# Fonte.net
KiCad netlist of a schematic drawn in Altium Designer
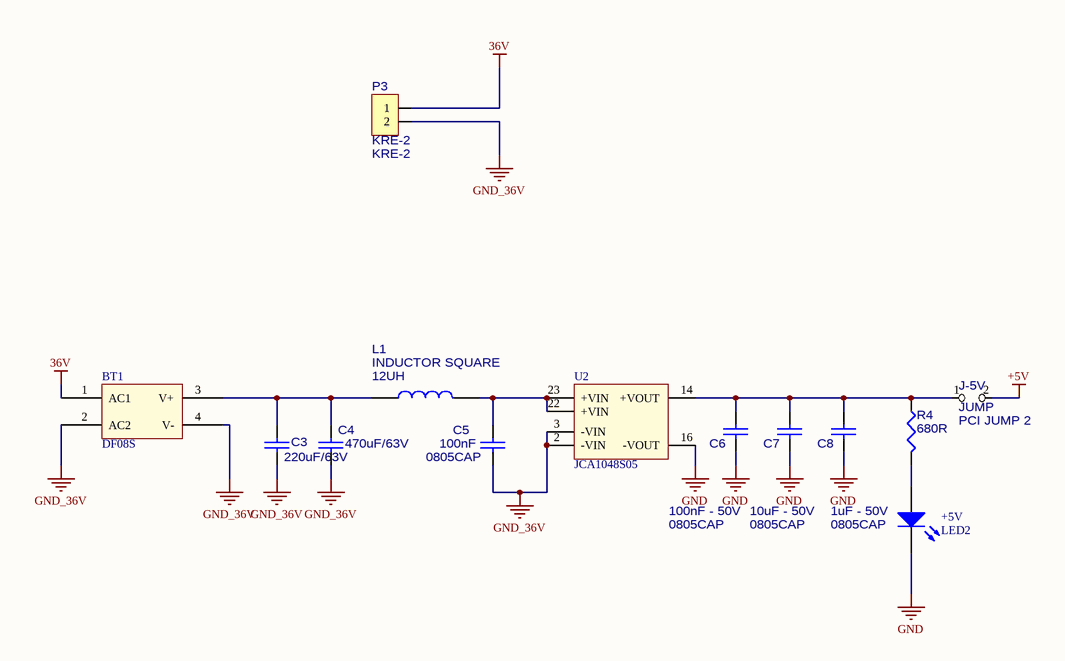
[diagram p0: Fonte.SchDoc]

(export (version "E")
  (design (tool "Eeschema 10.0.6"))
  (components
    (comp (ref "+5V")
      (value "LED2")
      (footprint "3.2X1.6X1.1")
      (description "Typical RED, GREEN, YELLOW, AMBER GaAs LED")
      (fields (field (name "PUBLISHER") "Altium Limited"))
      (libsource (lib "Miscellaneous Devices") (part "LED2"))
    )
    (comp (ref "BT1")
      (value "DF08S")
      (footprint "DF-S")
      (libsource (lib "Desafio_Hardware_Firmware_Nathania") (part "DF08S"))
    )
    (comp (ref "C3")
      (value "220uF/63V")
      (footprint "CAP_ELET_SMD_10x13.5")
      (libsource (lib "PMU_LIBRARY") (part "CAP"))
    )
    (comp (ref "C4")
      (value "470uF/63V")
      (footprint "CAP_ELET_SMD_10x13.5")
      (libsource (lib "PMU_LIBRARY") (part "CAP"))
    )
    (comp (ref "C5") (value "100nF") (footprint "0805CAP") (libsource (lib "PMU_LIBRARY") (part "CAP")))
    (comp (ref "C6") (value "100nF - 50V") (footprint "0805CAP") (libsource (lib "PMU_LIBRARY") (part "CAP")))
    (comp (ref "C7") (value "10uF - 50V") (footprint "0805CAP") (libsource (lib "PMU_LIBRARY") (part "CAP")))
    (comp (ref "C8") (value "1uF - 50V") (footprint "0805CAP") (libsource (lib "PMU_LIBRARY") (part "CAP")))
    (comp (ref "J-5V") (value "JUMP") (footprint "PCI JUMP 2") (libsource (lib "EMANUEL") (part "JUMP")))
    (comp (ref "L1")
      (value "12UH")
      (footprint "INDUCTOR SQUARE")
      (description "Inductor")
      (fields (field (name "Comment") "470UH"))
      (libsource (lib "*") (part "IND"))
    )
    (comp (ref "P3")
      (value "KRE-2")
      (footprint "KRE-2")
      (libsource (lib "Desafio_Hardware_Firmware_Nathania") (part "CON2_2_2"))
    )
    (comp (ref "R4")
      (value "680R")
      (footprint "0805RES")
      (description "2.2 Ohm 5% 1/16W 0603 RES SMT")
      (libsource (lib "EMANUEL") (part "Res0805"))
    )
    (comp (ref "U2")
      (value "JCA1048S05")
      (footprint "SCW05")
      (libsource (lib "TELEMETRIA_U_M_V1.0") (part "SCW05"))
    )
  )
  (nets
    (net (code "1") (name "+5V") (class "Default") (node (ref "J-5V") (pin "2") (pintype "passive")))
    (net (code "2") (name "36V") (class "Default")
      (node (ref "BT1") (pin "1") (pinfunction "AC1_1") (pintype "passive"))
      (node (ref "P3") (pin "1") (pinfunction "1_1") (pintype "passive"))
    )
    (net (code "3") (name "GND") (class "Default")
      (node (ref "+5V") (pin "2") (pinfunction "K_2") (pintype "passive"))
      (node (ref "C6") (pin "2") (pintype "passive"))
      (node (ref "C7") (pin "2") (pintype "passive"))
      (node (ref "C8") (pin "2") (pintype "passive"))
      (node (ref "U2") (pin "16") (pinfunction "-VOUT_16") (pintype "passive"))
    )
    (net (code "4") (name "GND_36V") (class "Default")
      (node (ref "BT1") (pin "2") (pinfunction "AC2_2") (pintype "passive"))
      (node (ref "BT1") (pin "4") (pinfunction "V-_4") (pintype "passive"))
      (node (ref "C3") (pin "1") (pintype "passive"))
      (node (ref "C4") (pin "1") (pintype "passive"))
      (node (ref "C5") (pin "2") (pintype "passive"))
      (node (ref "P3") (pin "2") (pinfunction "2_2") (pintype "passive"))
      (node (ref "U2") (pin "2") (pinfunction "-VIN_2") (pintype "passive"))
      (node (ref "U2") (pin "3") (pinfunction "-VIN_3") (pintype "passive"))
    )
    (net (code "5") (name "Net-(+5V-A)") (class "Default")
      (node (ref "+5V") (pin "1") (pinfunction "A_1") (pintype "passive"))
      (node (ref "R4") (pin "2") (pintype "passive"))
    )
    (net (code "6") (name "Net-(BT1-V+)") (class "Default")
      (node (ref "BT1") (pin "3") (pinfunction "V+_3") (pintype "passive"))
      (node (ref "C3") (pin "2") (pintype "passive"))
      (node (ref "C4") (pin "2") (pintype "passive"))
      (node (ref "L1") (pin "1") (pinfunction "1_1") (pintype "passive"))
    )
    (net (code "7") (name "Net-(C5-Pad1)") (class "Default")
      (node (ref "C5") (pin "1") (pintype "passive"))
      (node (ref "L1") (pin "2") (pinfunction "2_2") (pintype "passive"))
      (node (ref "U2") (pin "22") (pinfunction "+VIN_22") (pintype "passive"))
      (node (ref "U2") (pin "23") (pinfunction "+VIN_23") (pintype "passive"))
    )
    (net (code "8") (name "Net-(U2-+VOUT)") (class "Default")
      (node (ref "C6") (pin "1") (pintype "passive"))
      (node (ref "C7") (pin "1") (pintype "passive"))
      (node (ref "C8") (pin "1") (pintype "passive"))
      (node (ref "J-5V") (pin "1") (pintype "passive"))
      (node (ref "R4") (pin "1") (pintype "passive"))
      (node (ref "U2") (pin "14") (pinfunction "+VOUT_14") (pintype "passive"))
    )
    (net (code "9") (name "unconnected-(U2-NC-Pad9)") (class "Default")
      (node (ref "U2") (pin "9") (pinfunction "NC_9") (pintype "passive"))
    )
    (net (code "10") (name "unconnected-(U2-NC-Pad11)") (class "Default")
      (node (ref "U2") (pin "11") (pinfunction "NC_11") (pintype "passive"))
    )
  )
)
